# Temp.net
KiCad netlist of a schematic drawn in Altium Designer
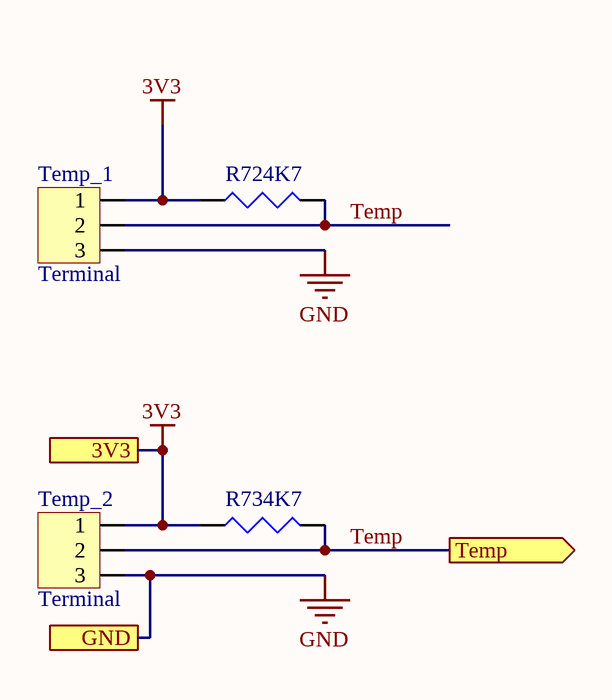
[diagram p0: Temp.SchDoc]

(export (version "E")
  (design (tool "Eeschema 10.0.6"))
  (components
    (comp (ref "R72")
      (value "4K7")
      (footprint "J1-0603")
      (description "Resistor")
      (fields (field (name "PUBLISHER") "Altium Limited"))
      (libsource (lib "Miscellaneous Devices") (part "Res3"))
    )
    (comp (ref "R73")
      (value "4K7")
      (footprint "J1-0603")
      (description "Resistor")
      (fields (field (name "PUBLISHER") "Altium Limited"))
      (libsource (lib "Miscellaneous Devices") (part "Res3"))
    )
    (comp (ref "Temp_1")
      (value "Terminal")
      (footprint "2,54 3pin terminal")
      (libsource (lib "SamacSys") (part "2,54 3pin terminal"))
    )
    (comp (ref "Temp_2")
      (value "Terminal")
      (footprint "2,54 3pin terminal")
      (libsource (lib "SamacSys") (part "2,54 3pin terminal"))
    )
  )
  (nets
    (net (code "1") (name "/Temp") (class "Default")
      (node (ref "R72") (pin "2") (pinfunction "2_2") (pintype "passive"))
      (node (ref "R73") (pin "2") (pinfunction "2_2") (pintype "passive"))
      (node (ref "Temp_1") (pin "2") (pinfunction "2_2") (pintype "passive"))
      (node (ref "Temp_2") (pin "2") (pinfunction "2_2") (pintype "passive"))
    )
    (net (code "2") (name "3V3") (class "Default")
      (node (ref "R72") (pin "1") (pinfunction "1_1") (pintype "passive"))
      (node (ref "R73") (pin "1") (pinfunction "1_1") (pintype "passive"))
      (node (ref "Temp_1") (pin "1") (pinfunction "1_1") (pintype "passive"))
      (node (ref "Temp_2") (pin "1") (pinfunction "1_1") (pintype "passive"))
    )
    (net (code "3") (name "GND") (class "Default")
      (node (ref "Temp_1") (pin "3") (pinfunction "3_3") (pintype "passive"))
      (node (ref "Temp_2") (pin "3") (pinfunction "3_3") (pintype "passive"))
    )
  )
)
